# Haar_Primal.net
KiCad netlist of a schematic drawn in EAGLE
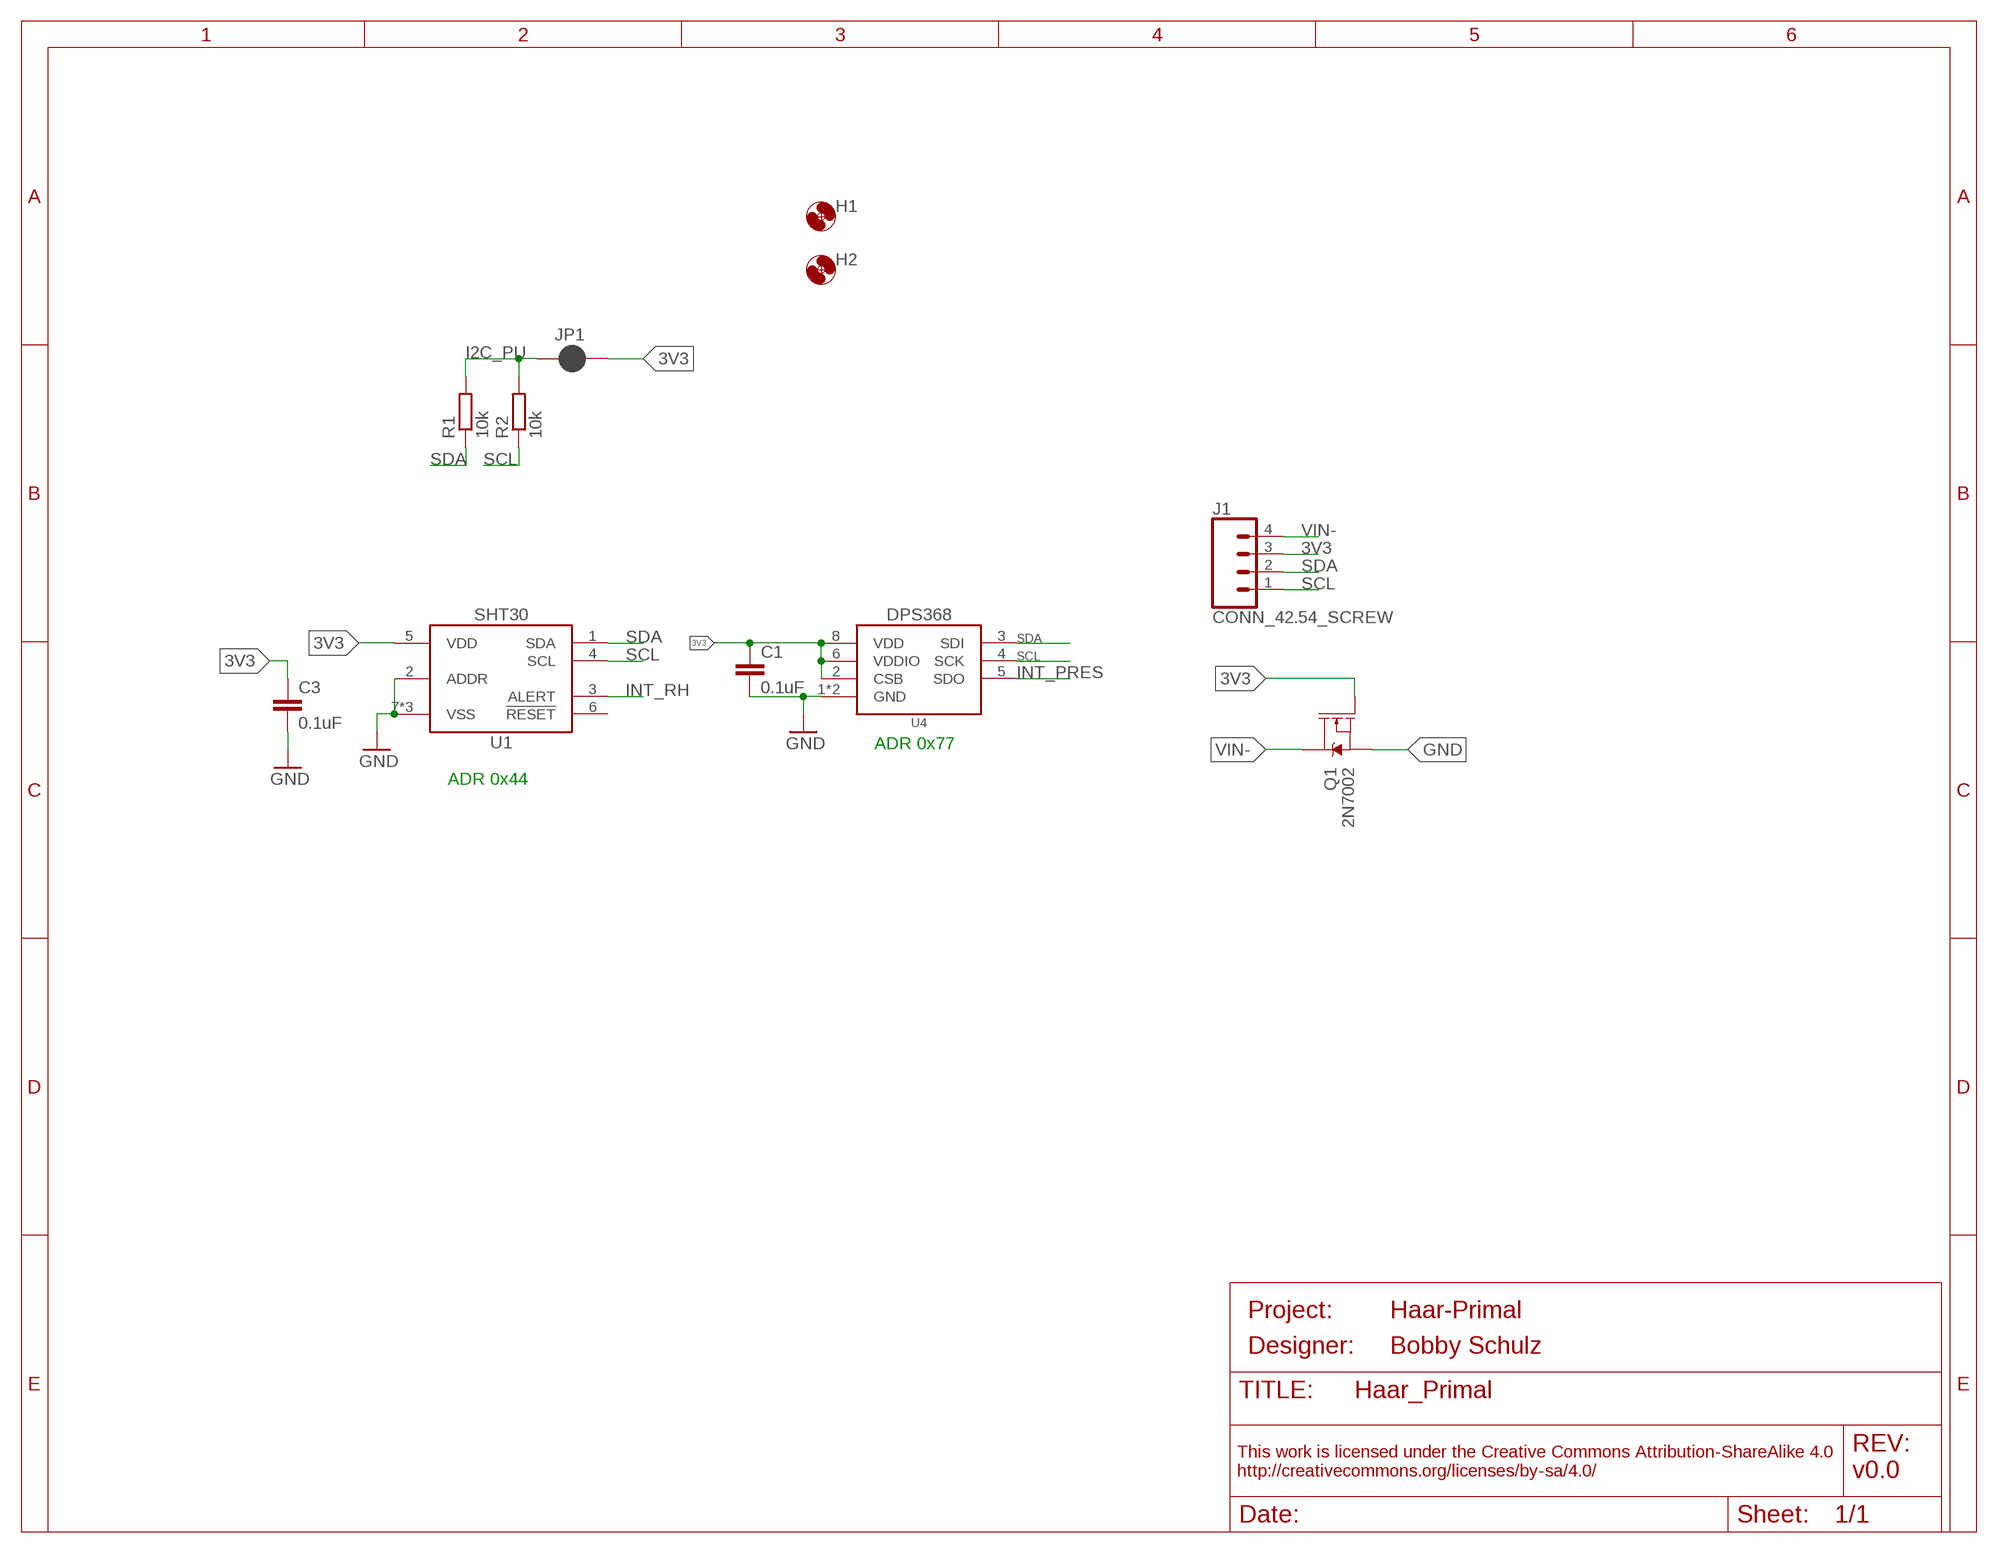
[diagram p0: schematic, sheet 1]

(export (version "E")
  (design (tool "Eeschema 10.0.6"))
  (components
    (comp (ref "C1")
      (value "0.1uF")
      (footprint "eagle-import:C0603")
      (fields (field (name "MF") "Murata") (field (name "MPN") "GCM188R71E104KA57D"))
      (libsource (lib "eagle-import") (part "C-EUC06030.1UF"))
    )
    (comp (ref "C3")
      (value "0.1uF")
      (footprint "eagle-import:C0603")
      (fields (field (name "MF") "Murata") (field (name "MPN") "GCM188R71E104KA57D"))
      (libsource (lib "eagle-import") (part "C-EUC06030.1UF"))
    )
    (comp (ref "H1")
      (value "MOUNTING_HOLE2_NP")
      (footprint "eagle-import:2_56")
      (libsource (lib "eagle-import") (part "MOUNTING_HOLE2_NP"))
    )
    (comp (ref "H2")
      (value "MOUNTING_HOLE2_NP")
      (footprint "eagle-import:2_56")
      (libsource (lib "eagle-import") (part "MOUNTING_HOLE2_NP"))
    )
    (comp (ref "J1")
      (value "CONN_42.54_SCREW")
      (footprint "eagle-import:1X04_SCREW")
      (fields (field (name "MF") "On Shore") (field (name "MPN") "OSTVN04A150"))
      (libsource (lib "eagle-import") (part "CONN_42.54_SCREW"))
    )
    (comp (ref "JP1")
      (value "JUMPER-SMT_2_NC_PASTE_SILK")
      (footprint "eagle-import:SMT-JUMPER_2_NC_PASTE_SILK")
      (libsource (lib "eagle-import") (part "JUMPER-SMT_2_NC_PASTE_SILK"))
    )
    (comp (ref "Q1")
      (value "2N7002")
      (footprint "eagle-import:SOT323")
      (fields (field (name "MF") "Diodes Incorporated") (field (name "MPN") "2N7002W-7-F"))
      (libsource (lib "eagle-import") (part "MOSFET-NCH-2N7002PW"))
    )
    (comp (ref "R1")
      (value "10k")
      (footprint "eagle-import:R0603")
      (fields (field (name "MF") "Yageo") (field (name "MPN") "RC0603FR-0710KL"))
      (libsource (lib "eagle-import") (part "R-EU_R060310K"))
    )
    (comp (ref "R2")
      (value "10k")
      (footprint "eagle-import:R0603")
      (fields (field (name "MF") "Yageo") (field (name "MPN") "RC0603FR-0710KL"))
      (libsource (lib "eagle-import") (part "R-EU_R060310K"))
    )
    (comp (ref "U1")
      (value "SHT30DFN")
      (footprint "eagle-import:DFN_8_2.5X2.5")
      (fields
        (field (name "DISP") "SHT30")
        (field (name "MF") "Sensirion")
        (field (name "MPN") "SHT30-DIS-F2.5KS")
      )
      (libsource (lib "eagle-import") (part "SHT3DFN0"))
    )
    (comp (ref "U4")
      (value "DPS368")
      (footprint "eagle-import:PG-VLGA-8")
      (fields
        (field (name "DISP") "DPS368")
        (field (name "MF") "Infineon")
        (field (name "MPN") "DPS368XTSA1")
      )
      (libsource (lib "eagle-import") (part "DPS368"))
    )
  )
  (nets
    (net (code "1") (name "/I2C_PU") (class "Default")
      (node (ref "JP1") (pin "1") (pinfunction "1_1") (pintype "passive"))
      (node (ref "R1") (pin "2") (pinfunction "2_2") (pintype "passive"))
      (node (ref "R2") (pin "2") (pinfunction "2_2") (pintype "passive"))
    )
    (net (code "2") (name "/INT_PRES") (class "Default")
      (node (ref "U4") (pin "5") (pinfunction "SDO_5") (pintype "bidirectional"))
    )
    (net (code "3") (name "/INT_RH") (class "Default")
      (node (ref "U1") (pin "3") (pinfunction "ALERT_3") (pintype "output"))
    )
    (net (code "4") (name "/SCL") (class "Default")
      (node (ref "J1") (pin "1") (pinfunction "1_1") (pintype "passive"))
      (node (ref "R2") (pin "1") (pinfunction "1_1") (pintype "passive"))
      (node (ref "U1") (pin "4") (pinfunction "SCL_4") (pintype "input"))
      (node (ref "U4") (pin "4") (pinfunction "SCK_4") (pintype "bidirectional"))
    )
    (net (code "5") (name "/SDA") (class "Default")
      (node (ref "J1") (pin "2") (pinfunction "2_2") (pintype "passive"))
      (node (ref "R1") (pin "1") (pinfunction "1_1") (pintype "passive"))
      (node (ref "U1") (pin "1") (pinfunction "SDA_1") (pintype "bidirectional"))
      (node (ref "U4") (pin "3") (pinfunction "SDI_3") (pintype "bidirectional"))
    )
    (net (code "6") (name "3V3") (class "Default")
      (node (ref "C1") (pin "1") (pinfunction "1_1") (pintype "passive"))
      (node (ref "C3") (pin "1") (pinfunction "1_1") (pintype "passive"))
      (node (ref "J1") (pin "3") (pinfunction "3_3") (pintype "passive"))
      (node (ref "JP1") (pin "2") (pinfunction "2_2") (pintype "passive"))
      (node (ref "Q1") (pin "1") (pinfunction "G_1") (pintype "bidirectional"))
      (node (ref "U1") (pin "5") (pinfunction "VDD_5") (pintype "power_in"))
      (node (ref "U4") (pin "2") (pinfunction "CSB_2") (pintype "bidirectional"))
      (node (ref "U4") (pin "6") (pinfunction "VDDIO_6") (pintype "bidirectional"))
      (node (ref "U4") (pin "8") (pinfunction "VDD_8") (pintype "power_in"))
    )
    (net (code "7") (name "GND") (class "Default")
      (node (ref "C1") (pin "2") (pinfunction "2_2") (pintype "passive"))
      (node (ref "C3") (pin "2") (pinfunction "2_2") (pintype "passive"))
      (node (ref "Q1") (pin "2") (pinfunction "S_2") (pintype "bidirectional"))
      (node (ref "U1") (pin "2") (pinfunction "ADDR_2") (pintype "input"))
      (node (ref "U1") (pin "7") (pinfunction "VSS_7") (pintype "power_in"))
      (node (ref "U1") (pin "8") (pinfunction "VSS_8") (pintype "power_in"))
      (node (ref "U1") (pin "EP") (pinfunction "VSS_EP") (pintype "power_in"))
      (node (ref "U4") (pin "1") (pinfunction "GND_1") (pintype "power_in"))
      (node (ref "U4") (pin "7") (pinfunction "GND_7") (pintype "power_in"))
    )
    (net (code "8") (name "VIN-") (class "Default")
      (node (ref "J1") (pin "4") (pinfunction "4_4") (pintype "passive"))
      (node (ref "Q1") (pin "3") (pinfunction "D_3") (pintype "bidirectional"))
    )
    (net (code "9") (name "unconnected-(U1-~{RESET}-Pad6)") (class "Default")
      (node (ref "U1") (pin "6") (pinfunction "~{RESET}_6") (pintype "input"))
    )
  )
)
